# 12_-_JETSON_CON.net
KiCad netlist of a schematic drawn in Altium Designer
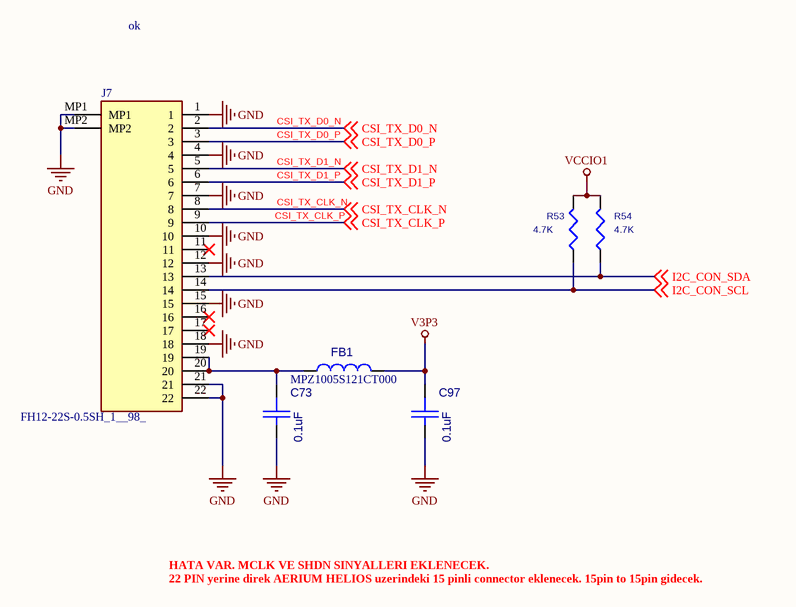
[diagram p0: 12 - JETSON_CON.SchDoc]

(export (version "E")
  (design (tool "Eeschema 10.0.6"))
  (components
    (comp (ref "C73")
      (value "0.1uF")
      (footprint "C0201")
      (description "CAP CER 0.1UF 25V 10% X5R 0201")
      (fields
        (field (name "MANUFACTURER") "Murata")
        (field (name "MANUFACTURER PART NUMBER") "GRM033R61E104KE14J")
      )
      (libsource (lib "*") (part "CAP_1"))
    )
    (comp (ref "C97")
      (value "0.1uF")
      (footprint "C0201")
      (description "CAP CER 0.1UF 25V 10% X5R 0201")
      (fields
        (field (name "MANUFACTURER") "Murata")
        (field (name "MANUFACTURER PART NUMBER") "GRM033R61E104KE14J")
      )
      (libsource (lib "*") (part "CAP_1"))
    )
    (comp (ref "FB1")
      (value "MPZ1005S121CT000")
      (footprint "FB0402")
      (description "FERRITE BEAD 120 OHM 0402 1LN")
      (fields (field (name "MANUFACTURER") "TDK Corporation"))
      (libsource (lib "*") (part "INDUCTOR_1"))
    )
    (comp (ref "J7")
      (value "FH12-22S-0.5SH_1__98_")
      (footprint "FH1222S05SH198")
      (description "Connector")
      (fields
        (field (name "MANUFACTURER_PART_NUMBER") "FH12-22S-0.5SH(1)(98)")
        (field (name "MOUSER PART NUMBER") "798-FH1222S05SH198")
      )
      (libsource (lib "Chronos") (part "FH12-22S-0.5SH_1__98_"))
    )
    (comp (ref "R53") (value "4.7K") (footprint "r0402") (libsource (lib "*") (part "RESISTOR")))
    (comp (ref "R54") (value "4.7K") (footprint "r0402") (libsource (lib "*") (part "RESISTOR")))
  )
  (nets
    (net (code "1") (name "CSI_TX_CLK_N") (class "Default")
      (node (ref "J7") (pin "8") (pinfunction "8_8") (pintype "passive"))
    )
    (net (code "2") (name "CSI_TX_CLK_P") (class "Default")
      (node (ref "J7") (pin "9") (pinfunction "9_9") (pintype "passive"))
    )
    (net (code "3") (name "CSI_TX_D0_N") (class "Default")
      (node (ref "J7") (pin "2") (pinfunction "2_2") (pintype "passive"))
    )
    (net (code "4") (name "CSI_TX_D0_P") (class "Default")
      (node (ref "J7") (pin "3") (pinfunction "3_3") (pintype "passive"))
    )
    (net (code "5") (name "CSI_TX_D1_N") (class "Default")
      (node (ref "J7") (pin "5") (pinfunction "5_5") (pintype "passive"))
    )
    (net (code "6") (name "CSI_TX_D1_P") (class "Default")
      (node (ref "J7") (pin "6") (pinfunction "6_6") (pintype "passive"))
    )
    (net (code "7") (name "GND") (class "Default")
      (node (ref "C73") (pin "2") (pinfunction "2_2") (pintype "passive"))
      (node (ref "C97") (pin "2") (pinfunction "2_2") (pintype "passive"))
      (node (ref "J7") (pin "1") (pinfunction "1_1") (pintype "passive"))
      (node (ref "J7") (pin "10") (pinfunction "10_10") (pintype "passive"))
      (node (ref "J7") (pin "12") (pinfunction "12_12") (pintype "passive"))
      (node (ref "J7") (pin "15") (pinfunction "15_15") (pintype "passive"))
      (node (ref "J7") (pin "18") (pinfunction "18_18") (pintype "passive"))
      (node (ref "J7") (pin "21") (pinfunction "21_21") (pintype "passive"))
      (node (ref "J7") (pin "22") (pinfunction "22_22") (pintype "passive"))
      (node (ref "J7") (pin "4") (pinfunction "4_4") (pintype "passive"))
      (node (ref "J7") (pin "7") (pinfunction "7_7") (pintype "passive"))
      (node (ref "J7") (pin "MP1") (pinfunction "MP1_MP1") (pintype "passive"))
      (node (ref "J7") (pin "MP2") (pinfunction "MP2_MP2") (pintype "passive"))
    )
    (net (code "8") (name "I2C_CON_SCL") (class "Default")
      (node (ref "J7") (pin "14") (pinfunction "14_14") (pintype "passive"))
      (node (ref "R53") (pin "1") (pinfunction "1_1") (pintype "passive"))
    )
    (net (code "9") (name "I2C_CON_SDA") (class "Default")
      (node (ref "J7") (pin "13") (pinfunction "13_13") (pintype "passive"))
      (node (ref "R54") (pin "1") (pinfunction "1_1") (pintype "passive"))
    )
    (net (code "10") (name "Net-(C73-Pad1)") (class "Default")
      (node (ref "C73") (pin "1") (pinfunction "1_1") (pintype "passive"))
      (node (ref "FB1") (pin "2") (pinfunction "2_2") (pintype "passive"))
      (node (ref "J7") (pin "19") (pinfunction "19_19") (pintype "passive"))
      (node (ref "J7") (pin "20") (pinfunction "20_20") (pintype "passive"))
    )
    (net (code "11") (name "V3P3") (class "Default")
      (node (ref "C97") (pin "1") (pinfunction "1_1") (pintype "passive"))
      (node (ref "FB1") (pin "1") (pinfunction "1_1") (pintype "passive"))
    )
    (net (code "12") (name "VCCIO1") (class "Default")
      (node (ref "R53") (pin "2") (pinfunction "2_2") (pintype "passive"))
      (node (ref "R54") (pin "2") (pinfunction "2_2") (pintype "passive"))
    )
    (net (code "13") (name "unconnected-(J7-Pad11)") (class "Default")
      (node (ref "J7") (pin "11") (pinfunction "11_11") (pintype "passive+no_connect"))
    )
    (net (code "14") (name "unconnected-(J7-Pad16)") (class "Default")
      (node (ref "J7") (pin "16") (pinfunction "16_16") (pintype "passive+no_connect"))
    )
    (net (code "15") (name "unconnected-(J7-Pad17)") (class "Default")
      (node (ref "J7") (pin "17") (pinfunction "17_17") (pintype "passive+no_connect"))
    )
  )
)
